# AltiiumSTM32_Shwematic.net
KiCad netlist of a schematic drawn in Altium Designer
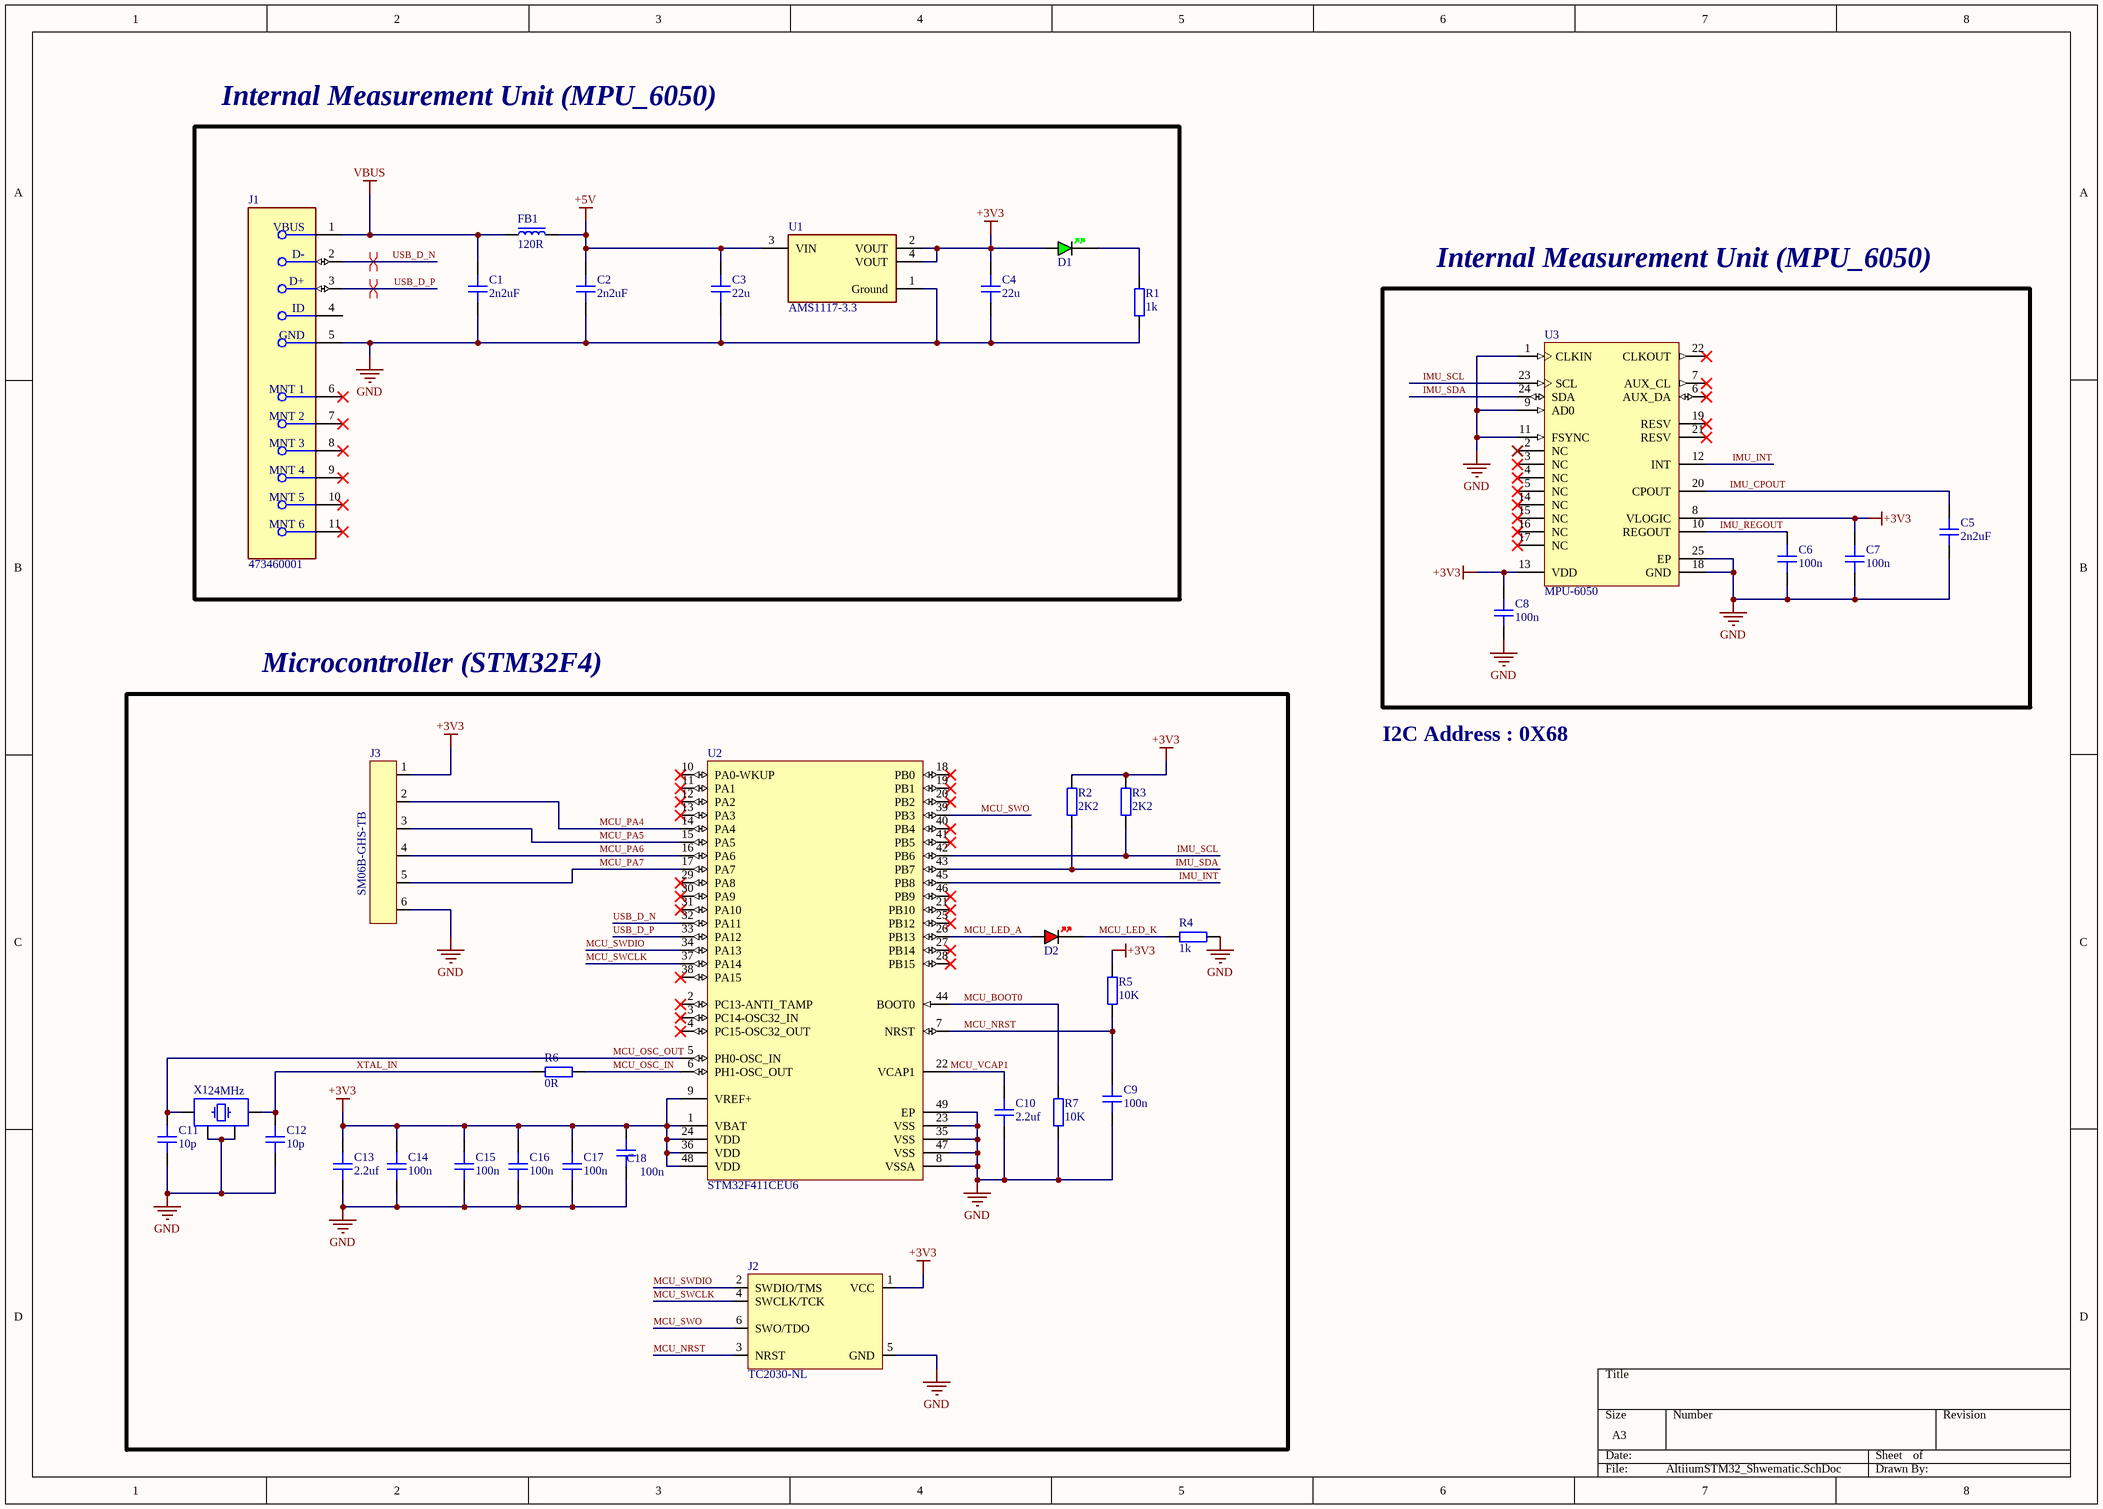
[diagram p0: AltiiumSTM32_Shwematic.SchDoc]

(export (version "E")
  (design (tool "Eeschema 10.0.6"))
  (components
    (comp (ref "C1")
      (value "2n2uF")
      (footprint "CAP_0603")
      (description "Capacitor SMD 0603")
      (libsource (lib "Schematic-Lib-PhilsLab") (part "CAP_0603"))
    )
    (comp (ref "C2")
      (value "2n2uF")
      (footprint "CAP_0603")
      (description "Capacitor SMD 0603")
      (libsource (lib "Schematic-Lib-PhilsLab") (part "CAP_0603"))
    )
    (comp (ref "C3")
      (value "22u")
      (footprint "CAP_0805")
      (description "Capacitor SMD 0805")
      (libsource (lib "Schematic-Lib-PhilsLab") (part "CAP_0805"))
    )
    (comp (ref "C4")
      (value "22u")
      (footprint "CAP_0805")
      (description "Capacitor SMD 0805")
      (libsource (lib "Schematic-Lib-PhilsLab") (part "CAP_0805"))
    )
    (comp (ref "C5")
      (value "2n2uF")
      (footprint "CAP_0603")
      (description "Capacitor SMD 0603")
      (libsource (lib "Schematic-Lib-PhilsLab") (part "CAP_0603"))
    )
    (comp (ref "C6")
      (value "100n")
      (footprint "CAP_0402")
      (description "Capacitor SMD 0402")
      (libsource (lib "Schematic-Lib-PhilsLab") (part "CAP_0402"))
    )
    (comp (ref "C7")
      (value "100n")
      (footprint "CAP_0402")
      (description "Capacitor SMD 0402")
      (libsource (lib "Schematic-Lib-PhilsLab") (part "CAP_0402"))
    )
    (comp (ref "C8")
      (value "100n")
      (footprint "CAP_0402")
      (description "Capacitor SMD 0402")
      (libsource (lib "Schematic-Lib-PhilsLab") (part "CAP_0402"))
    )
    (comp (ref "C9")
      (value "100n")
      (footprint "CAP_0402")
      (description "Capacitor SMD 0402")
      (libsource (lib "Schematic-Lib-PhilsLab") (part "CAP_0402"))
    )
    (comp (ref "C10")
      (value "2.2uf")
      (footprint "CAP_0603")
      (description "Capacitor SMD 0603")
      (libsource (lib "Schematic-Lib-PhilsLab") (part "CAP_0603"))
    )
    (comp (ref "C11")
      (value "10p")
      (footprint "CAP_0402")
      (description "Capacitor SMD 0402")
      (libsource (lib "Schematic-Lib-PhilsLab") (part "CAP_0402"))
    )
    (comp (ref "C12")
      (value "10p")
      (footprint "CAP_0402")
      (description "Capacitor SMD 0402")
      (libsource (lib "Schematic-Lib-PhilsLab") (part "CAP_0402"))
    )
    (comp (ref "C13")
      (value "2.2uf")
      (footprint "CAP_0603")
      (description "Capacitor SMD 0603")
      (libsource (lib "Schematic-Lib-PhilsLab") (part "CAP_0603"))
    )
    (comp (ref "C14")
      (value "100n")
      (footprint "CAP_0402")
      (description "Capacitor SMD 0402")
      (libsource (lib "Schematic-Lib-PhilsLab") (part "CAP_0402"))
    )
    (comp (ref "C15")
      (value "100n")
      (footprint "CAP_0402")
      (description "Capacitor SMD 0402")
      (libsource (lib "Schematic-Lib-PhilsLab") (part "CAP_0402"))
    )
    (comp (ref "C16")
      (value "100n")
      (footprint "CAP_0402")
      (description "Capacitor SMD 0402")
      (libsource (lib "Schematic-Lib-PhilsLab") (part "CAP_0402"))
    )
    (comp (ref "C17")
      (value "100n")
      (footprint "CAP_0402")
      (description "Capacitor SMD 0402")
      (libsource (lib "Schematic-Lib-PhilsLab") (part "CAP_0402"))
    )
    (comp (ref "C18")
      (value "100n")
      (footprint "CAP_0402")
      (description "Capacitor SMD 0402")
      (libsource (lib "Schematic-Lib-PhilsLab") (part "CAP_0402"))
    )
    (comp (ref "D1")
      (value "GREEN")
      (footprint "LED_0402_GREEN")
      (description "LED 0402 GREEN SMD")
      (libsource (lib "Schematic-Lib-PhilsLab") (part "LED_0402_GREEN"))
    )
    (comp (ref "D2")
      (value "RED")
      (footprint "LED_0402_RED")
      (description "LED 0402 RED SMD")
      (libsource (lib "Schematic-Lib-PhilsLab") (part "LED_0402_RED"))
    )
    (comp (ref "FB1")
      (value "120R")
      (footprint "FB_0603")
      (description "Ferrite Bead SMD 0603")
      (libsource (lib "Schematic-Lib-PhilsLab") (part "FB_0603"))
    )
    (comp (ref "J1")
      (value "473460001")
      (footprint "FP-473460001-MFG")
      (description "CONN RCPT USB2.0 MICRO B SMD R/A")
      (fields
        (field (name "OCTOPART") "https://octopart.com/47346-0001-molex-7164928")
        (field (name "MANUFACTURER") "Molex")
      )
      (libsource (lib "Altium Content Vault") (part "53ae1f1d9b557310b43ca686e5bb76a"))
    )
    (comp (ref "J2")
      (value "TC2030-NL")
      (footprint "TC2030-NL-FP")
      (description "Tag-Connect No-Solder SWD Debug Connector (No Legs) DO NOT PLACE")
      (fields
        (field (name "MANUFACTURER") "Tag-Connect")
        (field (name "MANUFACTURER PART NUMBER") "TC2030-NL-FP")
      )
      (libsource (lib "Schematic-Lib-PhilsLab") (part "TC2030-NL"))
    )
    (comp (ref "J3")
      (value "SM06B-GHS-TB")
      (footprint "SM06B-GHS-TB")
      (description "Header Connector 6 Position 1.25MM Pitch SMD Horizontal JST GH")
      (fields (field (name "MANUFACTURER") "JST"))
      (libsource (lib "Schematic-Lib-PhilsLab") (part "SM06B-GHS-TB"))
    )
    (comp (ref "R1")
      (value "1k")
      (footprint "RES_0402")
      (description "Resistor SMD 0402")
      (libsource (lib "Schematic-Lib-PhilsLab") (part "RES_0402"))
    )
    (comp (ref "R2")
      (value "2K2")
      (footprint "RES_0402")
      (description "Resistor SMD 0402")
      (libsource (lib "Schematic-Lib-PhilsLab") (part "RES_0402"))
    )
    (comp (ref "R3")
      (value "2K2")
      (footprint "RES_0402")
      (description "Resistor SMD 0402")
      (libsource (lib "Schematic-Lib-PhilsLab") (part "RES_0402"))
    )
    (comp (ref "R4")
      (value "1k")
      (footprint "RES_0402")
      (description "Resistor SMD 0402")
      (libsource (lib "Schematic-Lib-PhilsLab") (part "RES_0402"))
    )
    (comp (ref "R5")
      (value "10K")
      (footprint "RES_0402")
      (description "Resistor SMD 0402")
      (libsource (lib "Schematic-Lib-PhilsLab") (part "RES_0402"))
    )
    (comp (ref "R6")
      (value "0R")
      (footprint "RES_0201")
      (description "Resistor SMD 0201")
      (libsource (lib "Schematic-Lib-PhilsLab") (part "RES_0201"))
    )
    (comp (ref "R7")
      (value "10K")
      (footprint "RES_0402")
      (description "Resistor SMD 0402")
      (libsource (lib "Schematic-Lib-PhilsLab") (part "RES_0402"))
    )
    (comp (ref "U1")
      (value "AMS1117-3.3")
      (footprint "FP-AMS1117-IPC_C")
      (description "LDO Voltage Regulators 1A, 3.3V")
      (fields
        (field (name "OCTOPART") "https://octopart.com/ams1117-3.3-advanced+monolithic+systems-25899300")
        (field (name "MANUFACTURER") "Advanced Monolithic Systems")
      )
      (libsource (lib "Altium Content Vault") (part "8bdbb5f8e77002000e30dd2845d0354"))
    )
    (comp (ref "U2")
      (value "STM32F411CEU6")
      (footprint "STM-UFQFPN48_L")
      (libsource (lib "Altium Content Vault") (part "MC-ARM-STM32F411-UFQFPN48"))
    )
    (comp (ref "U3")
      (value "MPU-6050")
      (footprint "IS-QFN-24_V")
      (fields (field (name "MANUFACTURER") "InvenSense"))
      (libsource (lib "Altium Content Vault") (part "IS-MPU-6050-QFN-24"))
    )
    (comp (ref "X1")
      (value "24MHz")
      (footprint "XTAL_3225")
      (description "Crystal SMD 24MHz 10PPM 7pF 3225")
      (fields
        (field (name "MANUFACTURER") "Epson")
        (field (name "MANUFACTURER PART NUMBER") "TSX-3225 24.0000MF15X-AC")
      )
      (libsource (lib "Schematic-Lib-PhilsLab") (part "TSX-3225_24.0000MF15X-AC"))
    )
  )
  (nets
    (net (code "1") (name "+3V3") (class "Default")
      (node (ref "C13") (pin "2") (pinfunction "2_2") (pintype "passive"))
      (node (ref "C14") (pin "2") (pinfunction "2_2") (pintype "passive"))
      (node (ref "C15") (pin "2") (pinfunction "2_2") (pintype "passive"))
      (node (ref "C16") (pin "2") (pinfunction "2_2") (pintype "passive"))
      (node (ref "C17") (pin "2") (pinfunction "2_2") (pintype "passive"))
      (node (ref "C18") (pin "2") (pinfunction "2_2") (pintype "passive"))
      (node (ref "C4") (pin "2") (pinfunction "2_2") (pintype "passive"))
      (node (ref "C7") (pin "2") (pinfunction "2_2") (pintype "passive"))
      (node (ref "C8") (pin "2") (pinfunction "2_2") (pintype "passive"))
      (node (ref "D1") (pin "A") (pinfunction "A_A") (pintype "passive"))
      (node (ref "J2") (pin "1") (pinfunction "VCC_1") (pintype "passive"))
      (node (ref "J3") (pin "1") (pinfunction "1_1") (pintype "passive"))
      (node (ref "R2") (pin "2") (pinfunction "2_2") (pintype "passive"))
      (node (ref "R3") (pin "2") (pinfunction "2_2") (pintype "passive"))
      (node (ref "R5") (pin "2") (pinfunction "2_2") (pintype "passive"))
      (node (ref "U1") (pin "2") (pinfunction "VOUT_2") (pintype "passive"))
      (node (ref "U1") (pin "4") (pinfunction "VOUT_4") (pintype "passive"))
      (node (ref "U2") (pin "1") (pinfunction "VBAT_1") (pintype "power_in"))
      (node (ref "U2") (pin "24") (pinfunction "VDD_24") (pintype "power_in"))
      (node (ref "U2") (pin "36") (pinfunction "VDD_36") (pintype "power_in"))
      (node (ref "U2") (pin "48") (pinfunction "VDD_48") (pintype "power_in"))
      (node (ref "U2") (pin "9") (pinfunction "VREF+_9") (pintype "power_in"))
      (node (ref "U3") (pin "13") (pinfunction "VDD_13") (pintype "power_in"))
      (node (ref "U3") (pin "8") (pinfunction "VLOGIC_8") (pintype "power_in"))
    )
    (net (code "2") (name "+5V") (class "Default")
      (node (ref "C2") (pin "2") (pinfunction "2_2") (pintype "passive"))
      (node (ref "C3") (pin "2") (pinfunction "2_2") (pintype "passive"))
      (node (ref "FB1") (pin "2") (pinfunction "2_2") (pintype "passive"))
      (node (ref "U1") (pin "3") (pinfunction "VIN_3") (pintype "power_in"))
    )
    (net (code "3") (name "/IMU_CPOUT") (class "Default")
      (node (ref "C5") (pin "2") (pinfunction "2_2") (pintype "passive"))
      (node (ref "U3") (pin "20") (pinfunction "CPOUT_20") (pintype "passive"))
    )
    (net (code "4") (name "/IMU_INT") (class "Default")
      (node (ref "U2") (pin "45") (pinfunction "PB8_45") (pintype "bidirectional"))
      (node (ref "U3") (pin "12") (pinfunction "INT_12") (pintype "open_collector"))
    )
    (net (code "5") (name "/IMU_REGOUT") (class "Default")
      (node (ref "C6") (pin "2") (pinfunction "2_2") (pintype "passive"))
      (node (ref "U3") (pin "10") (pinfunction "REGOUT_10") (pintype "passive"))
    )
    (net (code "6") (name "/IMU_SCL") (class "Default")
      (node (ref "R3") (pin "1") (pinfunction "1_1") (pintype "passive"))
      (node (ref "U2") (pin "42") (pinfunction "PB6_42") (pintype "bidirectional"))
      (node (ref "U3") (pin "23") (pinfunction "SCL_23") (pintype "input"))
    )
    (net (code "7") (name "/IMU_SDA") (class "Default")
      (node (ref "R2") (pin "1") (pinfunction "1_1") (pintype "passive"))
      (node (ref "U2") (pin "43") (pinfunction "PB7_43") (pintype "bidirectional"))
      (node (ref "U3") (pin "24") (pinfunction "SDA_24") (pintype "bidirectional"))
    )
    (net (code "8") (name "/MCU_BOOT0") (class "Default")
      (node (ref "R7") (pin "2") (pinfunction "2_2") (pintype "passive"))
      (node (ref "U2") (pin "44") (pinfunction "BOOT0_44") (pintype "input"))
    )
    (net (code "9") (name "/MCU_LED_A") (class "Default")
      (node (ref "D2") (pin "A") (pinfunction "A_A") (pintype "passive"))
      (node (ref "U2") (pin "26") (pinfunction "PB13_26") (pintype "bidirectional"))
    )
    (net (code "10") (name "/MCU_LED_K") (class "Default")
      (node (ref "D2") (pin "K") (pinfunction "K_K") (pintype "passive"))
      (node (ref "R4") (pin "2") (pinfunction "2_2") (pintype "passive"))
    )
    (net (code "11") (name "/MCU_NRST") (class "Default")
      (node (ref "C9") (pin "2") (pinfunction "2_2") (pintype "passive"))
      (node (ref "J2") (pin "3") (pinfunction "NRST_3") (pintype "passive"))
      (node (ref "R5") (pin "1") (pinfunction "1_1") (pintype "passive"))
      (node (ref "U2") (pin "7") (pinfunction "NRST_7") (pintype "bidirectional"))
    )
    (net (code "12") (name "/MCU_OSC_IN") (class "Default")
      (node (ref "R6") (pin "2") (pinfunction "2_2") (pintype "passive"))
      (node (ref "U2") (pin "6") (pinfunction "PH1-OSC_OUT_6") (pintype "bidirectional"))
    )
    (net (code "13") (name "/MCU_OSC_OUT") (class "Default")
      (node (ref "C11") (pin "2") (pinfunction "2_2") (pintype "passive"))
      (node (ref "U2") (pin "5") (pinfunction "PH0-OSC_IN_5") (pintype "bidirectional"))
      (node (ref "X1") (pin "1") (pinfunction "1_1") (pintype "passive"))
    )
    (net (code "14") (name "/MCU_PA4") (class "Default")
      (node (ref "J3") (pin "2") (pinfunction "2_2") (pintype "passive"))
      (node (ref "U2") (pin "14") (pinfunction "PA4_14") (pintype "bidirectional"))
    )
    (net (code "15") (name "/MCU_PA5") (class "Default")
      (node (ref "J3") (pin "3") (pinfunction "3_3") (pintype "passive"))
      (node (ref "U2") (pin "15") (pinfunction "PA5_15") (pintype "bidirectional"))
    )
    (net (code "16") (name "/MCU_PA6") (class "Default")
      (node (ref "J3") (pin "4") (pinfunction "4_4") (pintype "passive"))
      (node (ref "U2") (pin "16") (pinfunction "PA6_16") (pintype "bidirectional"))
    )
    (net (code "17") (name "/MCU_PA7") (class "Default")
      (node (ref "J3") (pin "5") (pinfunction "5_5") (pintype "passive"))
      (node (ref "U2") (pin "17") (pinfunction "PA7_17") (pintype "bidirectional"))
    )
    (net (code "18") (name "/MCU_SWCLK") (class "Default")
      (node (ref "J2") (pin "4") (pinfunction "SWCLK/TCK_4") (pintype "passive"))
      (node (ref "U2") (pin "37") (pinfunction "PA14_37") (pintype "bidirectional"))
    )
    (net (code "19") (name "/MCU_SWDIO") (class "Default")
      (node (ref "J2") (pin "2") (pinfunction "SWDIO/TMS_2") (pintype "passive"))
      (node (ref "U2") (pin "34") (pinfunction "PA13_34") (pintype "bidirectional"))
    )
    (net (code "20") (name "/MCU_SWO") (class "Default")
      (node (ref "J2") (pin "6") (pinfunction "SWO/TDO_6") (pintype "passive"))
      (node (ref "U2") (pin "39") (pinfunction "PB3_39") (pintype "bidirectional"))
    )
    (net (code "21") (name "/MCU_VCAP1") (class "Default")
      (node (ref "C10") (pin "2") (pinfunction "2_2") (pintype "passive"))
      (node (ref "U2") (pin "22") (pinfunction "VCAP1_22") (pintype "passive"))
    )
    (net (code "22") (name "/USB_D_N") (class "Default")
      (node (ref "J1") (pin "2") (pinfunction "D-_2") (pintype "bidirectional"))
      (node (ref "U2") (pin "32") (pinfunction "PA11_32") (pintype "bidirectional"))
    )
    (net (code "23") (name "/USB_D_P") (class "Default")
      (node (ref "J1") (pin "3") (pinfunction "D+_3") (pintype "bidirectional"))
      (node (ref "U2") (pin "33") (pinfunction "PA12_33") (pintype "bidirectional"))
    )
    (net (code "24") (name "/XTAL_IN") (class "Default")
      (node (ref "C12") (pin "2") (pinfunction "2_2") (pintype "passive"))
      (node (ref "R6") (pin "1") (pinfunction "1_1") (pintype "passive"))
      (node (ref "X1") (pin "3") (pinfunction "3_3") (pintype "passive"))
    )
    (net (code "25") (name "GND") (class "Default")
      (node (ref "C1") (pin "1") (pinfunction "1_1") (pintype "passive"))
      (node (ref "C10") (pin "1") (pinfunction "1_1") (pintype "passive"))
      (node (ref "C11") (pin "1") (pinfunction "1_1") (pintype "passive"))
      (node (ref "C12") (pin "1") (pinfunction "1_1") (pintype "passive"))
      (node (ref "C13") (pin "1") (pinfunction "1_1") (pintype "passive"))
      (node (ref "C14") (pin "1") (pinfunction "1_1") (pintype "passive"))
      (node (ref "C15") (pin "1") (pinfunction "1_1") (pintype "passive"))
      (node (ref "C16") (pin "1") (pinfunction "1_1") (pintype "passive"))
      (node (ref "C17") (pin "1") (pinfunction "1_1") (pintype "passive"))
      (node (ref "C18") (pin "1") (pinfunction "1_1") (pintype "passive"))
      (node (ref "C2") (pin "1") (pinfunction "1_1") (pintype "passive"))
      (node (ref "C3") (pin "1") (pinfunction "1_1") (pintype "passive"))
      (node (ref "C4") (pin "1") (pinfunction "1_1") (pintype "passive"))
      (node (ref "C5") (pin "1") (pinfunction "1_1") (pintype "passive"))
      (node (ref "C6") (pin "1") (pinfunction "1_1") (pintype "passive"))
      (node (ref "C7") (pin "1") (pinfunction "1_1") (pintype "passive"))
      (node (ref "C8") (pin "1") (pinfunction "1_1") (pintype "passive"))
      (node (ref "C9") (pin "1") (pinfunction "1_1") (pintype "passive"))
      (node (ref "J1") (pin "5") (pinfunction "GND_5") (pintype "power_in"))
      (node (ref "J2") (pin "5") (pinfunction "GND_5") (pintype "passive"))
      (node (ref "J3") (pin "6") (pinfunction "6_6") (pintype "passive"))
      (node (ref "R1") (pin "1") (pinfunction "1_1") (pintype "passive"))
      (node (ref "R4") (pin "1") (pinfunction "1_1") (pintype "passive"))
      (node (ref "R7") (pin "1") (pinfunction "1_1") (pintype "passive"))
      (node (ref "U1") (pin "1") (pinfunction "Ground_1") (pintype "power_in"))
      (node (ref "U2") (pin "23") (pinfunction "VSS_23") (pintype "power_in"))
      (node (ref "U2") (pin "35") (pinfunction "VSS_35") (pintype "power_in"))
      (node (ref "U2") (pin "47") (pinfunction "VSS_47") (pintype "power_in"))
      (node (ref "U2") (pin "49") (pinfunction "EP_49") (pintype "power_in"))
      (node (ref "U2") (pin "8") (pinfunction "VSSA_8") (pintype "power_in"))
      (node (ref "U3") (pin "1") (pinfunction "CLKIN_1") (pintype "input"))
      (node (ref "U3") (pin "11") (pinfunction "FSYNC_11") (pintype "input"))
      (node (ref "U3") (pin "18") (pinfunction "GND_18") (pintype "power_in"))
      (node (ref "U3") (pin "25") (pinfunction "EP_25") (pintype "power_in"))
      (node (ref "U3") (pin "9") (pinfunction "AD0_9") (pintype "input"))
      (node (ref "X1") (pin "2") (pinfunction "2_2") (pintype "passive"))
      (node (ref "X1") (pin "4") (pinfunction "4_4") (pintype "passive"))
    )
    (net (code "26") (name "Net-(D1-PadK)") (class "Default")
      (node (ref "D1") (pin "K") (pinfunction "K_K") (pintype "passive"))
      (node (ref "R1") (pin "2") (pinfunction "2_2") (pintype "passive"))
    )
    (net (code "27") (name "VBUS") (class "Default")
      (node (ref "C1") (pin "2") (pinfunction "2_2") (pintype "passive"))
      (node (ref "FB1") (pin "1") (pinfunction "1_1") (pintype "passive"))
      (node (ref "J1") (pin "1") (pinfunction "VBUS_1") (pintype "power_in"))
    )
    (net (code "28") (name "unconnected-(J1-ID-Pad4)") (class "Default")
      (node (ref "J1") (pin "4") (pinfunction "ID_4") (pintype "passive"))
    )
    (net (code "29") (name "unconnected-(J1-MNT_1-Pad6)") (class "Default")
      (node (ref "J1") (pin "6") (pinfunction "MNT_1_6") (pintype "passive+no_connect"))
    )
    (net (code "30") (name "unconnected-(J1-MNT_2-Pad7)") (class "Default")
      (node (ref "J1") (pin "7") (pinfunction "MNT_2_7") (pintype "passive+no_connect"))
    )
    (net (code "31") (name "unconnected-(J1-MNT_3-Pad8)") (class "Default")
      (node (ref "J1") (pin "8") (pinfunction "MNT_3_8") (pintype "passive+no_connect"))
    )
    (net (code "32") (name "unconnected-(J1-MNT_4-Pad9)") (class "Default")
      (node (ref "J1") (pin "9") (pinfunction "MNT_4_9") (pintype "passive+no_connect"))
    )
    (net (code "33") (name "unconnected-(J1-MNT_5-Pad10)") (class "Default")
      (node (ref "J1") (pin "10") (pinfunction "MNT_5_10") (pintype "passive+no_connect"))
    )
    (net (code "34") (name "unconnected-(J1-MNT_6-Pad11)") (class "Default")
      (node (ref "J1") (pin "11") (pinfunction "MNT_6_11") (pintype "passive+no_connect"))
    )
    (net (code "35") (name "unconnected-(U2-PA0-WKUP-Pad10)") (class "Default")
      (node (ref "U2") (pin "10") (pinfunction "PA0-WKUP_10") (pintype "bidirectional+no_connect"))
    )
    (net (code "36") (name "unconnected-(U2-PA1-Pad11)") (class "Default")
      (node (ref "U2") (pin "11") (pinfunction "PA1_11") (pintype "bidirectional+no_connect"))
    )
    (net (code "37") (name "unconnected-(U2-PA2-Pad12)") (class "Default")
      (node (ref "U2") (pin "12") (pinfunction "PA2_12") (pintype "bidirectional+no_connect"))
    )
    (net (code "38") (name "unconnected-(U2-PA3-Pad13)") (class "Default")
      (node (ref "U2") (pin "13") (pinfunction "PA3_13") (pintype "bidirectional+no_connect"))
    )
    (net (code "39") (name "unconnected-(U2-PA8-Pad29)") (class "Default")
      (node (ref "U2") (pin "29") (pinfunction "PA8_29") (pintype "bidirectional+no_connect"))
    )
    (net (code "40") (name "unconnected-(U2-PA9-Pad30)") (class "Default")
      (node (ref "U2") (pin "30") (pinfunction "PA9_30") (pintype "bidirectional+no_connect"))
    )
    (net (code "41") (name "unconnected-(U2-PA10-Pad31)") (class "Default")
      (node (ref "U2") (pin "31") (pinfunction "PA10_31") (pintype "bidirectional+no_connect"))
    )
    (net (code "42") (name "unconnected-(U2-PA15-Pad38)") (class "Default")
      (node (ref "U2") (pin "38") (pinfunction "PA15_38") (pintype "bidirectional+no_connect"))
    )
    (net (code "43") (name "unconnected-(U2-PB0-Pad18)") (class "Default")
      (node (ref "U2") (pin "18") (pinfunction "PB0_18") (pintype "bidirectional+no_connect"))
    )
    (net (code "44") (name "unconnected-(U2-PB1-Pad19)") (class "Default")
      (node (ref "U2") (pin "19") (pinfunction "PB1_19") (pintype "bidirectional+no_connect"))
    )
    (net (code "45") (name "unconnected-(U2-PB2-Pad20)") (class "Default")
      (node (ref "U2") (pin "20") (pinfunction "PB2_20") (pintype "bidirectional+no_connect"))
    )
    (net (code "46") (name "unconnected-(U2-PB4-Pad40)") (class "Default")
      (node (ref "U2") (pin "40") (pinfunction "PB4_40") (pintype "bidirectional+no_connect"))
    )
    (net (code "47") (name "unconnected-(U2-PB5-Pad41)") (class "Default")
      (node (ref "U2") (pin "41") (pinfunction "PB5_41") (pintype "bidirectional+no_connect"))
    )
    (net (code "48") (name "unconnected-(U2-PB9-Pad46)") (class "Default")
      (node (ref "U2") (pin "46") (pinfunction "PB9_46") (pintype "bidirectional+no_connect"))
    )
    (net (code "49") (name "unconnected-(U2-PB10-Pad21)") (class "Default")
      (node (ref "U2") (pin "21") (pinfunction "PB10_21") (pintype "bidirectional+no_connect"))
    )
    (net (code "50") (name "unconnected-(U2-PB12-Pad25)") (class "Default")
      (node (ref "U2") (pin "25") (pinfunction "PB12_25") (pintype "bidirectional+no_connect"))
    )
    (net (code "51") (name "unconnected-(U2-PB14-Pad27)") (class "Default")
      (node (ref "U2") (pin "27") (pinfunction "PB14_27") (pintype "bidirectional+no_connect"))
    )
    (net (code "52") (name "unconnected-(U2-PB15-Pad28)") (class "Default")
      (node (ref "U2") (pin "28") (pinfunction "PB15_28") (pintype "bidirectional+no_connect"))
    )
    (net (code "53") (name "unconnected-(U2-PC13-ANTI_TAMP-Pad2)") (class "Default")
      (node (ref "U2") (pin "2") (pinfunction "PC13-ANTI_TAMP_2") (pintype "bidirectional+no_connect"))
    )
    (net (code "54") (name "unconnected-(U2-PC14-OSC32_IN-Pad3)") (class "Default")
      (node (ref "U2") (pin "3") (pinfunction "PC14-OSC32_IN_3") (pintype "bidirectional+no_connect"))
    )
    (net (code "55") (name "unconnected-(U2-PC15-OSC32_OUT-Pad4)") (class "Default")
      (node (ref "U2") (pin "4") (pinfunction "PC15-OSC32_OUT_4") (pintype "bidirectional+no_connect"))
    )
    (net (code "56") (name "unconnected-(U3-AUX_CL-Pad7)") (class "Default")
      (node (ref "U3") (pin "7") (pinfunction "AUX_CL_7") (pintype "output+no_connect"))
    )
    (net (code "57") (name "unconnected-(U3-AUX_DA-Pad6)") (class "Default")
      (node (ref "U3") (pin "6") (pinfunction "AUX_DA_6") (pintype "bidirectional+no_connect"))
    )
    (net (code "58") (name "unconnected-(U3-CLKOUT-Pad22)") (class "Default")
      (node (ref "U3") (pin "22") (pinfunction "CLKOUT_22") (pintype "output+no_connect"))
    )
    (net (code "59") (name "unconnected-(U3-NC-Pad2)") (class "Default")
      (node (ref "U3") (pin "2") (pinfunction "NC_2") (pintype "passive+no_connect"))
    )
    (net (code "60") (name "unconnected-(U3-NC-Pad3)") (class "Default")
      (node (ref "U3") (pin "3") (pinfunction "NC_3") (pintype "passive+no_connect"))
    )
    (net (code "61") (name "unconnected-(U3-NC-Pad4)") (class "Default")
      (node (ref "U3") (pin "4") (pinfunction "NC_4") (pintype "passive+no_connect"))
    )
    (net (code "62") (name "unconnected-(U3-NC-Pad5)") (class "Default")
      (node (ref "U3") (pin "5") (pinfunction "NC_5") (pintype "passive+no_connect"))
    )
    (net (code "63") (name "unconnected-(U3-NC-Pad14)") (class "Default")
      (node (ref "U3") (pin "14") (pinfunction "NC_14") (pintype "passive+no_connect"))
    )
    (net (code "64") (name "unconnected-(U3-NC-Pad15)") (class "Default")
      (node (ref "U3") (pin "15") (pinfunction "NC_15") (pintype "passive+no_connect"))
    )
    (net (code "65") (name "unconnected-(U3-NC-Pad16)") (class "Default")
      (node (ref "U3") (pin "16") (pinfunction "NC_16") (pintype "passive+no_connect"))
    )
    (net (code "66") (name "unconnected-(U3-NC-Pad17)") (class "Default")
      (node (ref "U3") (pin "17") (pinfunction "NC_17") (pintype "passive+no_connect"))
    )
    (net (code "67") (name "unconnected-(U3-RESV-Pad19)") (class "Default")
      (node (ref "U3") (pin "19") (pinfunction "RESV_19") (pintype "passive+no_connect"))
    )
    (net (code "68") (name "unconnected-(U3-RESV-Pad21)") (class "Default")
      (node (ref "U3") (pin "21") (pinfunction "RESV_21") (pintype "passive+no_connect"))
    )
  )
)
